# Pixel1_0_0.net
KiCad netlist of a schematic drawn in Altium Designer
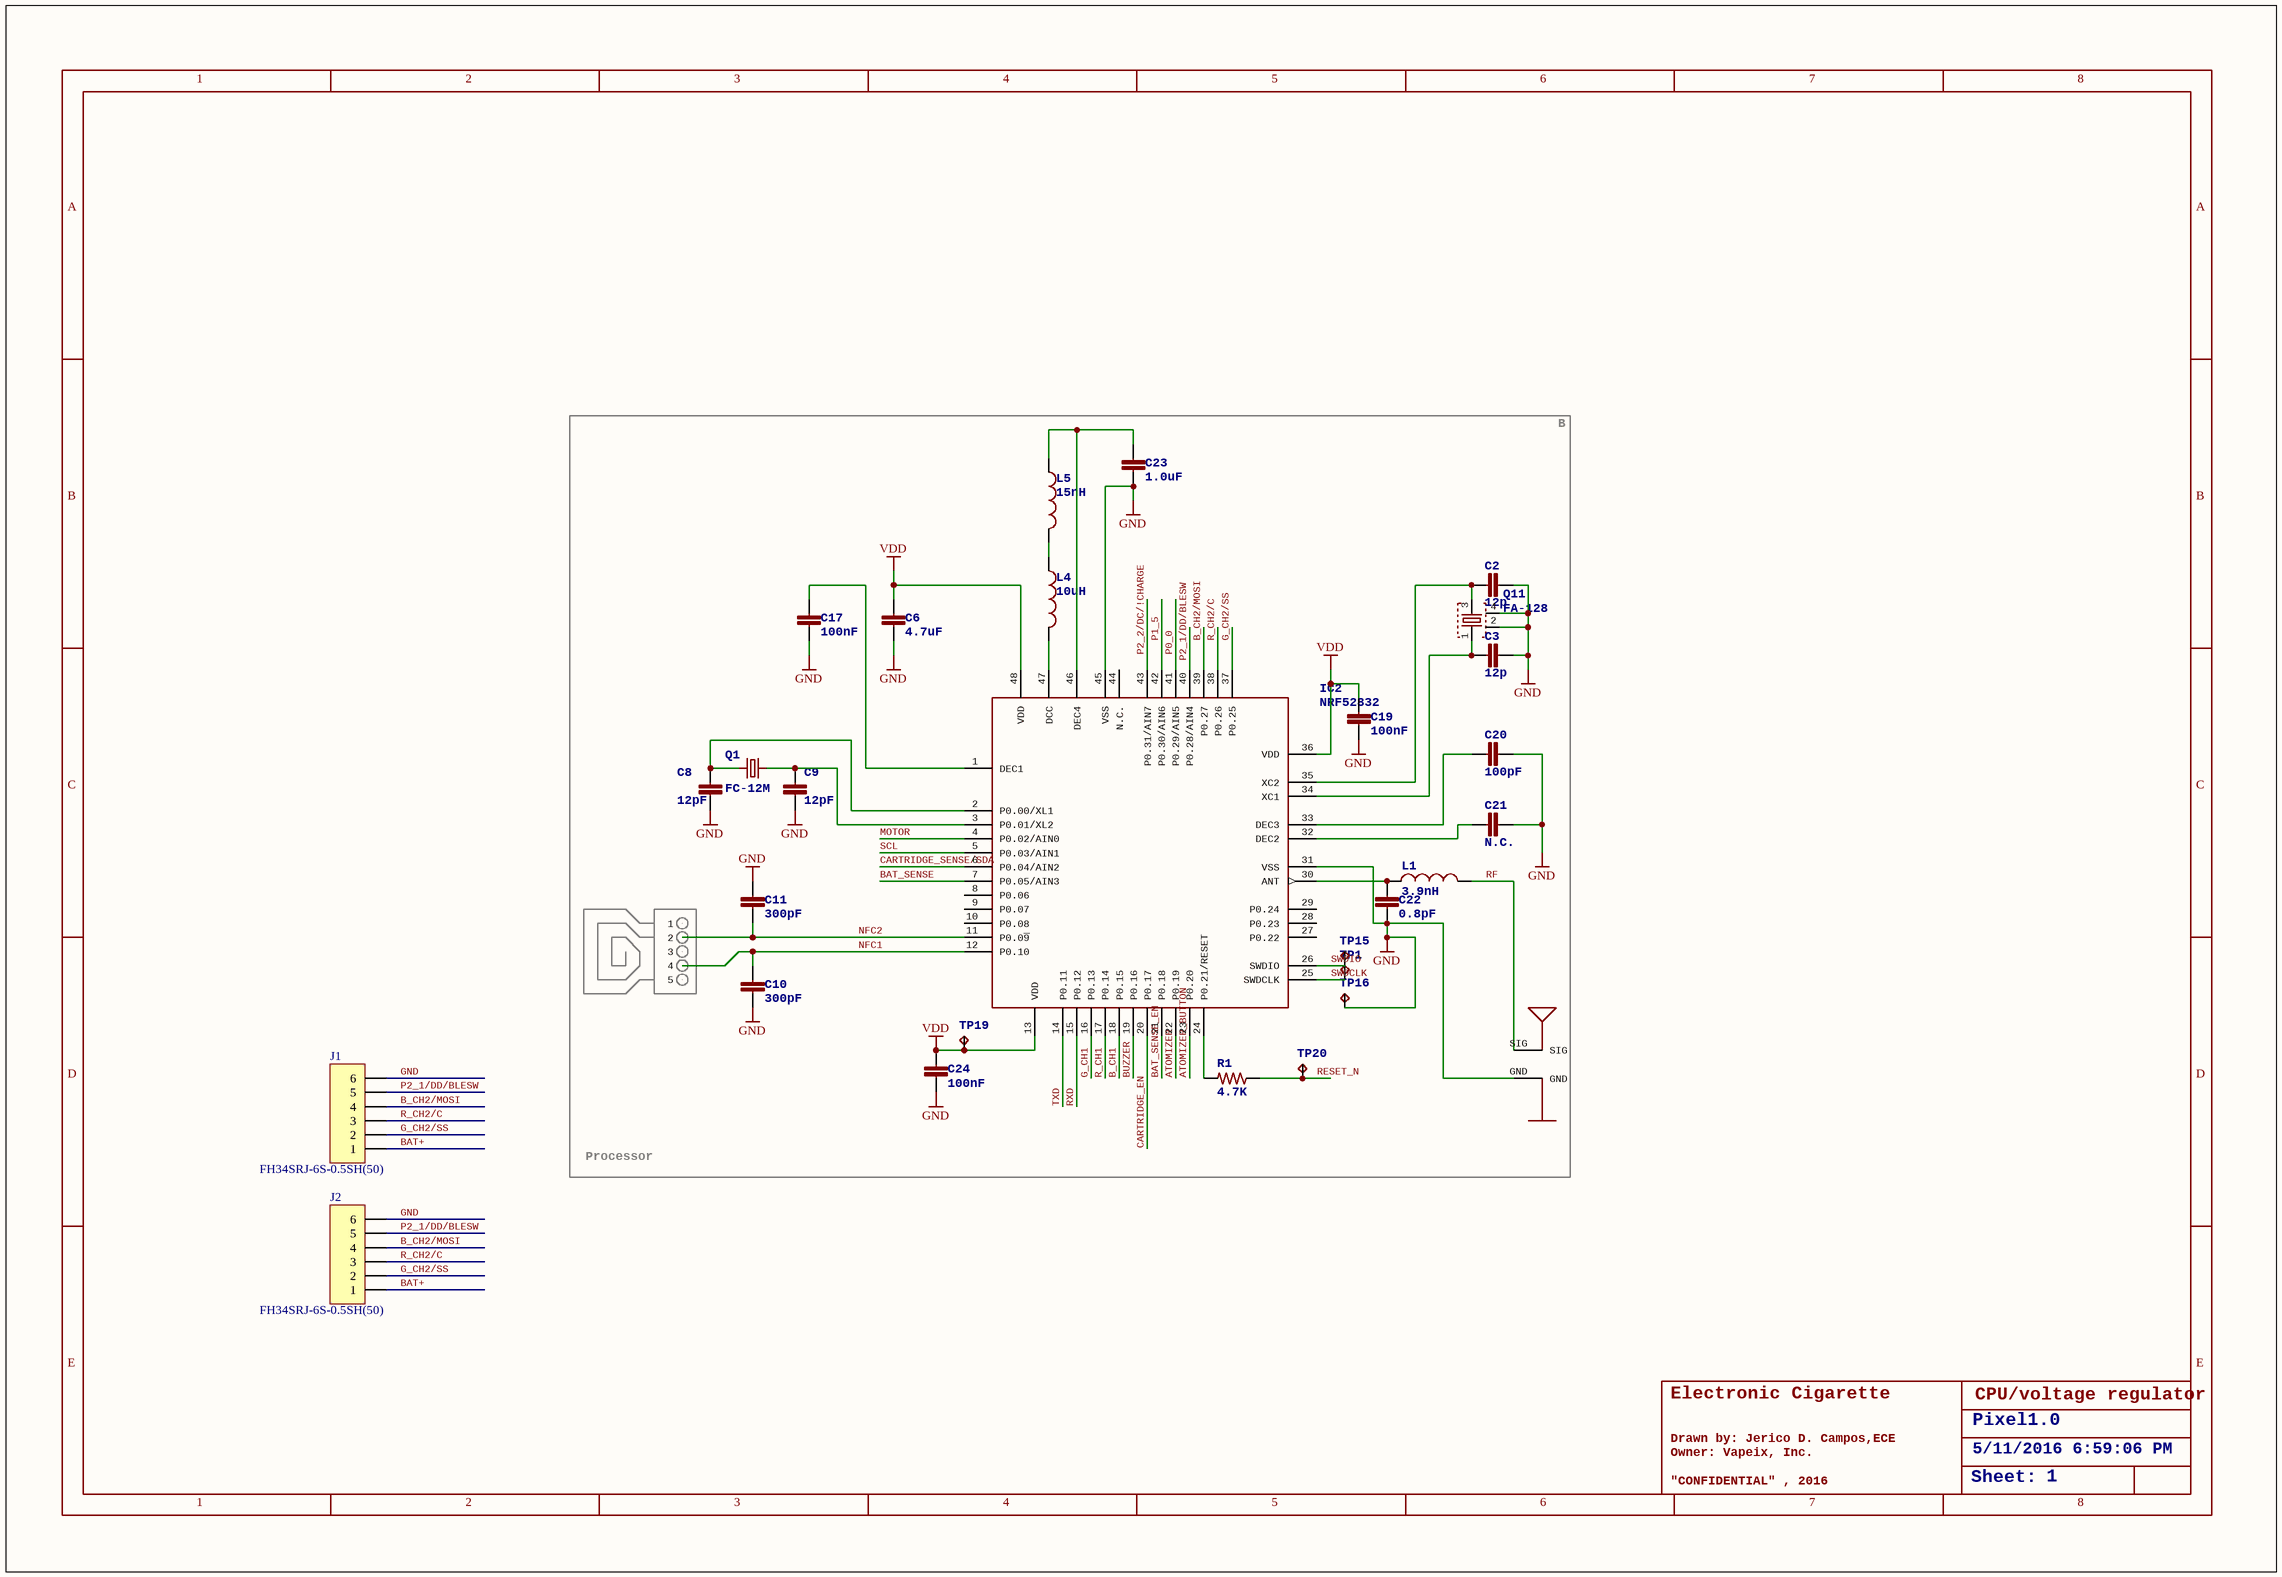
[diagram p0: Pixel1.0_0.SchDoc]

(export (version "E")
  (design (tool "Eeschema 10.0.6"))
  (components
    (comp (ref "ANT") (value "U.FL") (footprint "U.FL") (libsource (lib "Pixel1.0") (part "U.FL")))
    (comp (ref "C2")
      (value "12p")
      (footprint "C0201")
      (description "CAPACITOR, European symbol")
      (libsource (lib "") (part "C-EUC0201_3"))
    )
    (comp (ref "C3")
      (value "12p")
      (footprint "C0201")
      (description "CAPACITOR, European symbol")
      (libsource (lib "") (part "C-EUC0201_1"))
    )
    (comp (ref "C6")
      (value "4.7uF")
      (footprint "C0201")
      (description "CAPACITOR, European symbol")
      (libsource (lib "rcl") (part "C-EUC0201"))
    )
    (comp (ref "C8")
      (value "12pF")
      (footprint "C0201")
      (description "CAPACITOR, European symbol")
      (libsource (lib "rcl") (part "C-EUC0201"))
    )
    (comp (ref "C9")
      (value "12pF")
      (footprint "C0201")
      (description "CAPACITOR, European symbol")
      (libsource (lib "rcl") (part "C-EUC0201"))
    )
    (comp (ref "C10")
      (value "300pF")
      (footprint "C0201")
      (description "CAPACITOR, European symbol")
      (libsource (lib "rcl") (part "C-EUC0201"))
    )
    (comp (ref "C11")
      (value "300pF")
      (footprint "C0201")
      (description "CAPACITOR, European symbol")
      (libsource (lib "") (part "C-EUC0201_2"))
    )
    (comp (ref "C17")
      (value "100nF")
      (footprint "C0201")
      (description "CAPACITOR, European symbol")
      (libsource (lib "rcl") (part "C-EUC0201"))
    )
    (comp (ref "C19")
      (value "100nF")
      (footprint "C0201")
      (description "CAPACITOR, European symbol")
      (libsource (lib "rcl") (part "C-EUC0201"))
    )
    (comp (ref "C20")
      (value "100pF")
      (footprint "C0201")
      (description "CAPACITOR, European symbol")
      (libsource (lib "") (part "C-EUC0201_1"))
    )
    (comp (ref "C21")
      (value "N.C.")
      (footprint "C0201")
      (description "CAPACITOR, European symbol")
      (libsource (lib "") (part "C-EUC0201_1"))
    )
    (comp (ref "C22")
      (value "0.8pF")
      (footprint "C0201")
      (description "CAPACITOR, European symbol")
      (libsource (lib "rcl") (part "C-EUC0201"))
    )
    (comp (ref "C23")
      (value "1.0uF")
      (footprint "C0201")
      (description "CAPACITOR, European symbol")
      (libsource (lib "rcl") (part "C-EUC0201"))
    )
    (comp (ref "C24")
      (value "100nF")
      (footprint "C0201")
      (description "CAPACITOR, European symbol")
      (libsource (lib "rcl") (part "C-EUC0201"))
    )
    (comp (ref "IC2") (value "NRF52832") (footprint "QFN-48") (libsource (lib "FTDI") (part "NRF52832")))
    (comp (ref "J1")
      (value "FH34SRJ-6S-0.5SH(50)")
      (footprint "59453061110ECHLF")
      (description "WR-FPC 0.50mm SMT ZIF Horizontal Bottom Contact")
      (fields
        (field (name "MANUFACTURER") "Würth Elektronik eiSos GmbH")
        (field (name "PARTNO") "68710614522")
        (field (name "CREATED BY") "Karrer Zheng")
      )
      (libsource (lib "Components") (part "WE-ZIF Connector WR-FPC 68710614522"))
    )
    (comp (ref "J2")
      (value "FH34SRJ-6S-0.5SH(50)")
      (footprint "59453061110ECHLF")
      (description "WR-FPC 0.50mm SMT ZIF Horizontal Bottom Contact")
      (fields
        (field (name "MANUFACTURER") "Würth Elektronik eiSos GmbH")
        (field (name "PARTNO") "68710614522")
        (field (name "CREATED BY") "Karrer Zheng")
      )
      (libsource (lib "Components") (part "WE-ZIF Connector WR-FPC 68710614522"))
    )
    (comp (ref "L1") (value "3.9nH") (footprint "JE0402") (libsource (lib "vapeix") (part "LBEAD")))
    (comp (ref "L4") (value "10uH") (footprint "JE0402") (libsource (lib "vapeix") (part "LBEAD")))
    (comp (ref "L5") (value "15nH") (footprint "JE0402") (libsource (lib "vapeix") (part "LBEAD")))
    (comp (ref "Q1")
      (value "FC-12M")
      (footprint "FC-12M")
      (description "kHz RANGE CRYSTAL UNIT   LOW PROFILE SMDSource: Epson Toyocom FC-12M.pdf")
      (libsource (lib "crystal") (part "FC-12M"))
    )
    (comp (ref "Q11")
      (value "FA-128")
      (footprint "FA-128")
      (description "MHz RANGE CRYSTAL UNIT    Source: Epson Toyocom")
      (libsource (lib "crystal") (part "FA-128"))
    )
    (comp (ref "R1")
      (value "4.7K")
      (footprint "R0201")
      (description "RESISTOR, American symbol")
      (libsource (lib "rcl") (part "R-US_R0201"))
    )
    (comp (ref "TP1")
      (value "TPTP06R")
      (footprint "TP06R")
      (description "Test pad")
      (libsource (lib "testpad") (part "TPTP06R"))
    )
    (comp (ref "TP15")
      (value "TPTP06R")
      (footprint "TP06R")
      (description "Test pad")
      (libsource (lib "testpad") (part "TPTP06R"))
    )
    (comp (ref "TP16")
      (value "TPTP06R")
      (footprint "TP06R")
      (description "Test pad")
      (libsource (lib "testpad") (part "TPTP06R"))
    )
    (comp (ref "TP19")
      (value "TPTP06R")
      (footprint "TP06R")
      (description "Test pad")
      (libsource (lib "testpad") (part "TPTP06R"))
    )
    (comp (ref "TP20")
      (value "TPTP06R")
      (footprint "TP06R")
      (description "Test pad")
      (libsource (lib "testpad") (part "TPTP06R"))
    )
    (comp (ref "U$2")
      (value "NFCCONNECTORMOLEX_5PIN")
      (footprint "NFC.CONN")
      (libsource (lib "vapeix") (part "NFCCONNECTORMOLEX_5PIN"))
    )
  )
  (nets
    (net (code "1") (name "/ATOMIZER") (class "Default")
      (node (ref "IC2") (pin "22") (pinfunction "P0.19_22") (pintype "passive"))
    )
    (net (code "2") (name "/ATOMIZER_BUTTON") (class "Default")
      (node (ref "IC2") (pin "23") (pinfunction "P0.20_23") (pintype "passive"))
    )
    (net (code "3") (name "/BAT+") (class "Default")
      (node (ref "J1") (pin "1") (pinfunction "1_1") (pintype "passive"))
      (node (ref "J2") (pin "1") (pinfunction "1_1") (pintype "passive"))
    )
    (net (code "4") (name "/BAT_SENSE") (class "Default")
      (node (ref "IC2") (pin "7") (pinfunction "P0.05/AIN3_7") (pintype "passive"))
    )
    (net (code "5") (name "/BAT_SENSE_EN") (class "Default")
      (node (ref "IC2") (pin "21") (pinfunction "P0.18_21") (pintype "passive"))
    )
    (net (code "6") (name "/BUZZER") (class "Default")
      (node (ref "IC2") (pin "19") (pinfunction "P0.16_19") (pintype "passive"))
    )
    (net (code "7") (name "/B_CH1") (class "Default")
      (node (ref "IC2") (pin "18") (pinfunction "P0.15_18") (pintype "passive"))
    )
    (net (code "8") (name "/B_CH2{slash}MOSI") (class "Default")
      (node (ref "IC2") (pin "39") (pinfunction "P0.27_39") (pintype "passive"))
      (node (ref "J1") (pin "4") (pinfunction "4_4") (pintype "passive"))
      (node (ref "J2") (pin "4") (pinfunction "4_4") (pintype "passive"))
    )
    (net (code "9") (name "/CARTRIDGE_EN") (class "Default")
      (node (ref "IC2") (pin "20") (pinfunction "P0.17_20") (pintype "passive"))
    )
    (net (code "10") (name "/CARTRIDGE_SENSE{slash}SDA") (class "Default")
      (node (ref "IC2") (pin "6") (pinfunction "P0.04/AIN2_6") (pintype "passive"))
    )
    (net (code "11") (name "/G_CH1") (class "Default")
      (node (ref "IC2") (pin "16") (pinfunction "P0.13_16") (pintype "passive"))
    )
    (net (code "12") (name "/G_CH2{slash}SS") (class "Default")
      (node (ref "IC2") (pin "37") (pinfunction "P0.25_37") (pintype "passive"))
      (node (ref "J1") (pin "2") (pinfunction "2_2") (pintype "passive"))
      (node (ref "J2") (pin "2") (pinfunction "2_2") (pintype "passive"))
    )
    (net (code "13") (name "/MOTOR") (class "Default")
      (node (ref "IC2") (pin "4") (pinfunction "P0.02/AIN0_4") (pintype "passive"))
    )
    (net (code "14") (name "/NFC1") (class "Default")
      (node (ref "C10") (pin "1") (pinfunction "1_1") (pintype "passive"))
      (node (ref "IC2") (pin "12") (pinfunction "P0.10_12") (pintype "passive"))
      (node (ref "U$2") (pin "4") (pinfunction "4_4") (pintype "passive"))
    )
    (net (code "15") (name "/NFC2") (class "Default")
      (node (ref "C11") (pin "1") (pinfunction "1_1") (pintype "passive"))
      (node (ref "IC2") (pin "11") (pinfunction "P0.0~{9}_11") (pintype "passive"))
      (node (ref "U$2") (pin "2") (pinfunction "2_2") (pintype "passive"))
    )
    (net (code "16") (name "/P0_0") (class "Default")
      (node (ref "IC2") (pin "41") (pinfunction "P0.29/AIN5_41") (pintype "passive"))
    )
    (net (code "17") (name "/P1_5") (class "Default")
      (node (ref "IC2") (pin "42") (pinfunction "P0.30/AIN6_42") (pintype "passive"))
    )
    (net (code "18") (name "/P2_1{slash}DD{slash}BLESW") (class "Default")
      (node (ref "IC2") (pin "40") (pinfunction "P0.28/AIN4_40") (pintype "passive"))
      (node (ref "J1") (pin "5") (pinfunction "5_5") (pintype "passive"))
      (node (ref "J2") (pin "5") (pinfunction "5_5") (pintype "passive"))
    )
    (net (code "19") (name "/P2_2{slash}DC{slash}!CHARGE") (class "Default")
      (node (ref "IC2") (pin "43") (pinfunction "P0.31/AIN7_43") (pintype "passive"))
    )
    (net (code "20") (name "/RESET_N") (class "Default")
      (node (ref "R1") (pin "1") (pinfunction "1_1") (pintype "passive"))
      (node (ref "TP20") (pin "TP") (pinfunction "TP_TP") (pintype "passive"))
    )
    (net (code "21") (name "/RF") (class "Default")
      (node (ref "ANT") (pin "SIG") (pinfunction "SIG_SIG") (pintype "passive"))
      (node (ref "L1") (pin "2") (pinfunction "2_2") (pintype "passive"))
    )
    (net (code "22") (name "/RXD") (class "Default")
      (node (ref "IC2") (pin "15") (pinfunction "P0.12_15") (pintype "passive"))
    )
    (net (code "23") (name "/R_CH1") (class "Default")
      (node (ref "IC2") (pin "17") (pinfunction "P0.14_17") (pintype "passive"))
    )
    (net (code "24") (name "/R_CH2{slash}C") (class "Default")
      (node (ref "IC2") (pin "38") (pinfunction "P0.26_38") (pintype "passive"))
      (node (ref "J1") (pin "3") (pinfunction "3_3") (pintype "passive"))
      (node (ref "J2") (pin "3") (pinfunction "3_3") (pintype "passive"))
    )
    (net (code "25") (name "/SCL") (class "Default")
      (node (ref "IC2") (pin "5") (pinfunction "P0.03/AIN1_5") (pintype "passive"))
    )
    (net (code "26") (name "/SWDCLK") (class "Default")
      (node (ref "IC2") (pin "25") (pinfunction "SWDCLK_25") (pintype "open_collector"))
      (node (ref "TP1") (pin "TP") (pinfunction "TP_TP") (pintype "passive"))
    )
    (net (code "27") (name "/SWDIO") (class "Default")
      (node (ref "IC2") (pin "26") (pinfunction "SWDIO_26") (pintype "open_collector"))
      (node (ref "TP15") (pin "TP") (pinfunction "TP_TP") (pintype "passive"))
    )
    (net (code "28") (name "/TXD") (class "Default")
      (node (ref "IC2") (pin "14") (pinfunction "P0.11_14") (pintype "passive"))
    )
    (net (code "29") (name "GND") (class "Default")
      (node (ref "ANT") (pin "GND") (pinfunction "GND_GND") (pintype "passive"))
      (node (ref "C10") (pin "2") (pinfunction "2_2") (pintype "passive"))
      (node (ref "C11") (pin "2") (pinfunction "2_2") (pintype "passive"))
      (node (ref "C17") (pin "2") (pinfunction "2_2") (pintype "passive"))
      (node (ref "C19") (pin "2") (pinfunction "2_2") (pintype "passive"))
      (node (ref "C2") (pin "2") (pinfunction "2_2") (pintype "passive"))
      (node (ref "C20") (pin "1") (pinfunction "1_1") (pintype "passive"))
      (node (ref "C21") (pin "1") (pinfunction "1_1") (pintype "passive"))
      (node (ref "C22") (pin "2") (pinfunction "2_2") (pintype "passive"))
      (node (ref "C23") (pin "2") (pinfunction "2_2") (pintype "passive"))
      (node (ref "C24") (pin "2") (pinfunction "2_2") (pintype "passive"))
      (node (ref "C3") (pin "1") (pinfunction "1_1") (pintype "passive"))
      (node (ref "C6") (pin "2") (pinfunction "2_2") (pintype "passive"))
      (node (ref "C8") (pin "2") (pinfunction "2_2") (pintype "passive"))
      (node (ref "C9") (pin "2") (pinfunction "2_2") (pintype "passive"))
      (node (ref "IC2") (pin "31") (pinfunction "VSS_31") (pintype "power_in"))
      (node (ref "IC2") (pin "45") (pinfunction "VSS_45") (pintype "power_in"))
      (node (ref "J1") (pin "6") (pinfunction "6_6") (pintype "passive"))
      (node (ref "J2") (pin "6") (pinfunction "6_6") (pintype "passive"))
      (node (ref "Q11") (pin "2") (pinfunction "2_2") (pintype "passive"))
      (node (ref "Q11") (pin "4") (pinfunction "4_4") (pintype "passive"))
      (node (ref "TP16") (pin "TP") (pinfunction "TP_TP") (pintype "passive"))
    )
    (net (code "30") (name "Net-(IC2-ANT)") (class "Default")
      (node (ref "C22") (pin "1") (pinfunction "1_1") (pintype "passive"))
      (node (ref "IC2") (pin "30") (pinfunction "ANT_30") (pintype "output"))
      (node (ref "L1") (pin "1") (pinfunction "1_1") (pintype "passive"))
    )
    (net (code "31") (name "Net-(IC2-DCC)") (class "Default")
      (node (ref "IC2") (pin "47") (pinfunction "DCC_47") (pintype "power_in"))
      (node (ref "L4") (pin "2") (pinfunction "2_2") (pintype "passive"))
    )
    (net (code "32") (name "Net-(IC2-DEC1)") (class "Default")
      (node (ref "C17") (pin "1") (pinfunction "1_1") (pintype "passive"))
      (node (ref "IC2") (pin "1") (pinfunction "DEC1_1") (pintype "power_in"))
    )
    (net (code "33") (name "Net-(IC2-DEC2)") (class "Default")
      (node (ref "C21") (pin "2") (pinfunction "2_2") (pintype "passive"))
      (node (ref "IC2") (pin "32") (pinfunction "DEC2_32") (pintype "power_in"))
    )
    (net (code "34") (name "Net-(IC2-DEC3)") (class "Default")
      (node (ref "C20") (pin "2") (pinfunction "2_2") (pintype "passive"))
      (node (ref "IC2") (pin "33") (pinfunction "DEC3_33") (pintype "power_in"))
    )
    (net (code "35") (name "Net-(IC2-DEC4)") (class "Default")
      (node (ref "C23") (pin "1") (pinfunction "1_1") (pintype "passive"))
      (node (ref "IC2") (pin "46") (pinfunction "DEC4_46") (pintype "power_in"))
      (node (ref "L5") (pin "1") (pinfunction "1_1") (pintype "passive"))
    )
    (net (code "36") (name "Net-(IC2-P0.00{slash}XL1)") (class "Default")
      (node (ref "C8") (pin "1") (pinfunction "1_1") (pintype "passive"))
      (node (ref "IC2") (pin "2") (pinfunction "P0.00/XL1_2") (pintype "passive"))
      (node (ref "Q1") (pin "1") (pinfunction "1_1") (pintype "passive"))
    )
    (net (code "37") (name "Net-(IC2-P0.01{slash}XL2)") (class "Default")
      (node (ref "C9") (pin "1") (pinfunction "1_1") (pintype "passive"))
      (node (ref "IC2") (pin "3") (pinfunction "P0.01/XL2_3") (pintype "passive"))
      (node (ref "Q1") (pin "2") (pinfunction "2_2") (pintype "passive"))
    )
    (net (code "38") (name "Net-(IC2-P0.21{slash}RESET)") (class "Default")
      (node (ref "IC2") (pin "24") (pinfunction "P0.21/RESET_24") (pintype "passive"))
      (node (ref "R1") (pin "2") (pinfunction "2_2") (pintype "passive"))
    )
    (net (code "39") (name "Net-(IC2-XC1)") (class "Default")
      (node (ref "C3") (pin "2") (pinfunction "2_2") (pintype "passive"))
      (node (ref "IC2") (pin "34") (pinfunction "XC1_34") (pintype "open_collector"))
      (node (ref "Q11") (pin "1") (pinfunction "1_1") (pintype "passive"))
    )
    (net (code "40") (name "Net-(IC2-XC2)") (class "Default")
      (node (ref "C2") (pin "1") (pinfunction "1_1") (pintype "passive"))
      (node (ref "IC2") (pin "35") (pinfunction "XC2_35") (pintype "open_collector"))
      (node (ref "Q11") (pin "3") (pinfunction "3_3") (pintype "passive"))
    )
    (net (code "41") (name "Net-(L4-Pad1)") (class "Default")
      (node (ref "L4") (pin "1") (pinfunction "1_1") (pintype "passive"))
      (node (ref "L5") (pin "2") (pinfunction "2_2") (pintype "passive"))
    )
    (net (code "42") (name "VDD") (class "Default")
      (node (ref "C19") (pin "1") (pinfunction "1_1") (pintype "passive"))
      (node (ref "C24") (pin "1") (pinfunction "1_1") (pintype "passive"))
      (node (ref "C6") (pin "1") (pinfunction "1_1") (pintype "passive"))
      (node (ref "IC2") (pin "13") (pinfunction "VDD_13") (pintype "passive"))
      (node (ref "IC2") (pin "36") (pinfunction "VDD_36") (pintype "power_in"))
      (node (ref "IC2") (pin "48") (pinfunction "VDD_48") (pintype "power_in"))
      (node (ref "TP19") (pin "TP") (pinfunction "TP_TP") (pintype "passive"))
    )
    (net (code "43") (name "unconnected-(IC2-N.C.-Pad44)") (class "Default")
      (node (ref "IC2") (pin "44") (pinfunction "N.C._44") (pintype "passive"))
    )
    (net (code "44") (name "unconnected-(IC2-P0.06-Pad8)") (class "Default")
      (node (ref "IC2") (pin "8") (pinfunction "P0.06_8") (pintype "passive"))
    )
    (net (code "45") (name "unconnected-(IC2-P0.07-Pad9)") (class "Default")
      (node (ref "IC2") (pin "9") (pinfunction "P0.07_9") (pintype "passive"))
    )
    (net (code "46") (name "unconnected-(IC2-P0.08-Pad10)") (class "Default")
      (node (ref "IC2") (pin "10") (pinfunction "P0.08_10") (pintype "passive"))
    )
    (net (code "47") (name "unconnected-(IC2-P0.22-Pad27)") (class "Default")
      (node (ref "IC2") (pin "27") (pinfunction "P0.22_27") (pintype "passive"))
    )
    (net (code "48") (name "unconnected-(IC2-P0.23-Pad28)") (class "Default")
      (node (ref "IC2") (pin "28") (pinfunction "P0.23_28") (pintype "passive"))
    )
    (net (code "49") (name "unconnected-(IC2-P0.24-Pad29)") (class "Default")
      (node (ref "IC2") (pin "29") (pinfunction "P0.24_29") (pintype "passive"))
    )
    (net (code "50") (name "unconnected-(U$2-Pad1)") (class "Default")
      (node (ref "U$2") (pin "1") (pinfunction "1_1") (pintype "passive"))
    )
    (net (code "51") (name "unconnected-(U$2-Pad3)") (class "Default")
      (node (ref "U$2") (pin "3") (pinfunction "3_3") (pintype "passive"))
    )
    (net (code "52") (name "unconnected-(U$2-Pad5)") (class "Default")
      (node (ref "U$2") (pin "5") (pinfunction "5_5") (pintype "passive"))
    )
  )
)
